# SparkFun_Transceiver_Breakout_RPSMA.net
KiCad netlist of a schematic drawn in EAGLE
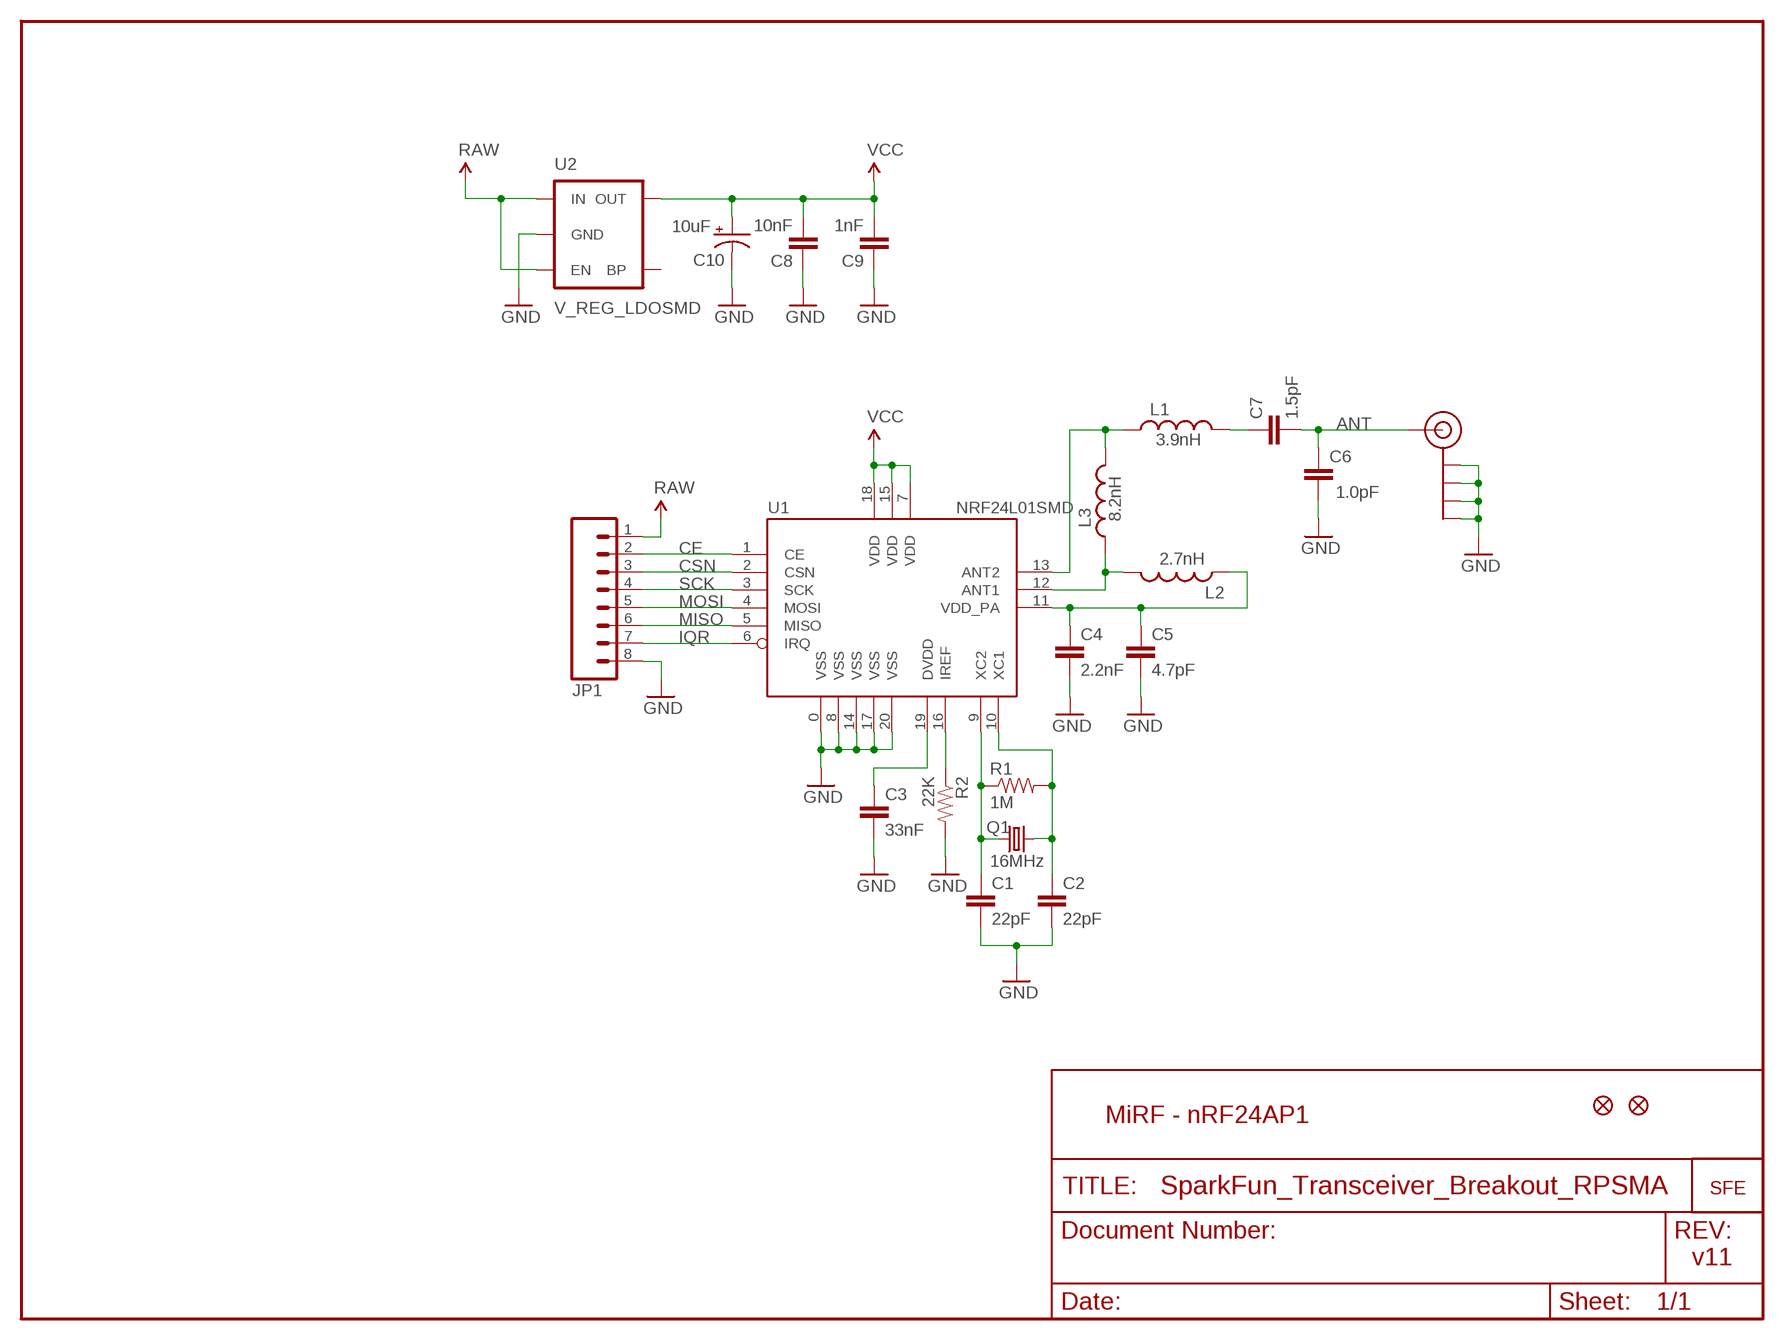
[diagram p0: schematic, sheet 1]

(export (version "E")
  (design (tool "Eeschema 10.0.6"))
  (components
    (comp (ref "C1")
      (value "22pF")
      (footprint "eagle-import:C0402")
      (libsource (lib "eagle-import") (part "CAP0402"))
    )
    (comp (ref "C2")
      (value "22pF")
      (footprint "eagle-import:C0402")
      (libsource (lib "eagle-import") (part "CAP0402"))
    )
    (comp (ref "C3")
      (value "33nF")
      (footprint "eagle-import:C0402")
      (libsource (lib "eagle-import") (part "CAP0402"))
    )
    (comp (ref "C4")
      (value "2.2nF")
      (footprint "eagle-import:C0402")
      (libsource (lib "eagle-import") (part "CAP0402"))
    )
    (comp (ref "C5")
      (value "4.7pF")
      (footprint "eagle-import:C0402")
      (libsource (lib "eagle-import") (part "CAP0402"))
    )
    (comp (ref "C6")
      (value "1.0pF")
      (footprint "eagle-import:C0402")
      (libsource (lib "eagle-import") (part "CAP0402"))
    )
    (comp (ref "C7")
      (value "1.5pF")
      (footprint "eagle-import:C0402")
      (libsource (lib "eagle-import") (part "CAP0402"))
    )
    (comp (ref "C8")
      (value "10nF")
      (footprint "eagle-import:C0402")
      (libsource (lib "eagle-import") (part "CAP0402"))
    )
    (comp (ref "C9")
      (value "1nF")
      (footprint "eagle-import:C0402")
      (libsource (lib "eagle-import") (part "CAP0402"))
    )
    (comp (ref "C10")
      (value "10uF")
      (footprint "eagle-import:EIA3216")
      (libsource (lib "eagle-import") (part "CAP_POL1206"))
    )
    (comp (ref "FID1")
      (value "FIDUCIALUFIDUCIAL")
      (footprint "eagle-import:MICRO-FIDUCIAL")
      (libsource (lib "eagle-import") (part "FIDUCIALUFIDUCIAL"))
    )
    (comp (ref "FID2")
      (value "FIDUCIALUFIDUCIAL")
      (footprint "eagle-import:MICRO-FIDUCIAL")
      (libsource (lib "eagle-import") (part "FIDUCIALUFIDUCIAL"))
    )
    (comp (ref "J$1")
      (value "SMA_EDGE")
      (footprint "eagle-import:SMA-EDGE")
      (libsource (lib "eagle-import") (part "SMA_EDGE"))
    )
    (comp (ref "JP1")
      (value "M08")
      (footprint "eagle-import:1X08")
      (libsource (lib "eagle-import") (part "M08"))
    )
    (comp (ref "L1")
      (value "3.9nH")
      (footprint "eagle-import:C0402")
      (libsource (lib "eagle-import") (part "INDUCTOR0402"))
    )
    (comp (ref "L2")
      (value "2.7nH")
      (footprint "eagle-import:C0402")
      (libsource (lib "eagle-import") (part "INDUCTOR0402"))
    )
    (comp (ref "L3")
      (value "8.2nH")
      (footprint "eagle-import:C0402")
      (libsource (lib "eagle-import") (part "INDUCTOR0402"))
    )
    (comp (ref "Q1")
      (value "16MHz")
      (footprint "eagle-import:CRYSTAL-SMD-5X3")
      (libsource (lib "eagle-import") (part "CRYSTAL5X3"))
    )
    (comp (ref "R1")
      (value "1M")
      (footprint "eagle-import:C0402")
      (libsource (lib "eagle-import") (part "RESISTOR0402"))
    )
    (comp (ref "R2")
      (value "22K")
      (footprint "eagle-import:C0402")
      (libsource (lib "eagle-import") (part "RESISTOR0402"))
    )
    (comp (ref "U$5")
      (value "LOGO-SFENEW")
      (footprint "eagle-import:SFE-NEW-WEBLOGO")
      (libsource (lib "eagle-import") (part "LOGO-SFENEW"))
    )
    (comp (ref "U1")
      (value "NRF24L01SMD")
      (footprint "eagle-import:QFN20")
      (libsource (lib "eagle-import") (part "NRF24L01SMD"))
    )
    (comp (ref "U2")
      (value "V_REG_LDOSMD")
      (footprint "eagle-import:SOT23-5")
      (libsource (lib "eagle-import") (part "V_REG_LDOSMD"))
    )
  )
  (nets
    (net (code "1") (name "/ANT") (class "Default")
      (node (ref "C6") (pin "2") (pinfunction "2_2") (pintype "passive"))
      (node (ref "C7") (pin "2") (pinfunction "2_2") (pintype "passive"))
      (node (ref "J$1") (pin "SIG") (pinfunction "SIGNAL_SIG") (pintype "bidirectional"))
    )
    (net (code "2") (name "/CE") (class "Default")
      (node (ref "JP1") (pin "2") (pinfunction "2_2") (pintype "passive"))
      (node (ref "U1") (pin "1") (pinfunction "CE_1") (pintype "input"))
    )
    (net (code "3") (name "/CSN") (class "Default")
      (node (ref "JP1") (pin "3") (pinfunction "3_3") (pintype "passive"))
      (node (ref "U1") (pin "2") (pinfunction "CSN_2") (pintype "input"))
    )
    (net (code "4") (name "/IQR") (class "Default")
      (node (ref "JP1") (pin "7") (pinfunction "7_7") (pintype "passive"))
      (node (ref "U1") (pin "6") (pinfunction "IRQ_6") (pintype "output"))
    )
    (net (code "5") (name "/MISO") (class "Default")
      (node (ref "JP1") (pin "6") (pinfunction "6_6") (pintype "passive"))
      (node (ref "U1") (pin "5") (pinfunction "MISO_5") (pintype "output"))
    )
    (net (code "6") (name "/MOSI") (class "Default")
      (node (ref "JP1") (pin "5") (pinfunction "5_5") (pintype "passive"))
      (node (ref "U1") (pin "4") (pinfunction "MOSI_4") (pintype "input"))
    )
    (net (code "7") (name "/SCK") (class "Default")
      (node (ref "JP1") (pin "4") (pinfunction "4_4") (pintype "passive"))
      (node (ref "U1") (pin "3") (pinfunction "SCK_3") (pintype "input"))
    )
    (net (code "8") (name "GND") (class "Default")
      (node (ref "C1") (pin "2") (pinfunction "2_2") (pintype "passive"))
      (node (ref "C10") (pin "C") (pinfunction "-_C") (pintype "passive"))
      (node (ref "C2") (pin "2") (pinfunction "2_2") (pintype "passive"))
      (node (ref "C3") (pin "2") (pinfunction "2_2") (pintype "passive"))
      (node (ref "C4") (pin "2") (pinfunction "2_2") (pintype "passive"))
      (node (ref "C5") (pin "2") (pinfunction "2_2") (pintype "passive"))
      (node (ref "C6") (pin "1") (pinfunction "1_1") (pintype "passive"))
      (node (ref "C8") (pin "1") (pinfunction "1_1") (pintype "passive"))
      (node (ref "C9") (pin "1") (pinfunction "1_1") (pintype "passive"))
      (node (ref "J$1") (pin "GND@0") (pinfunction "GND_GND@0") (pintype "bidirectional"))
      (node (ref "J$1") (pin "GND@1") (pinfunction "GND_GND@1") (pintype "bidirectional"))
      (node (ref "J$1") (pin "GND@2") (pinfunction "GND_GND@2") (pintype "bidirectional"))
      (node (ref "J$1") (pin "GND@3") (pinfunction "GND_GND@3") (pintype "bidirectional"))
      (node (ref "JP1") (pin "8") (pinfunction "8_8") (pintype "passive"))
      (node (ref "R2") (pin "2") (pinfunction "2_2") (pintype "passive"))
      (node (ref "U1") (pin "0") (pinfunction "VSS_0") (pintype "power_in"))
      (node (ref "U1") (pin "14") (pinfunction "VSS_14") (pintype "power_in"))
      (node (ref "U1") (pin "17") (pinfunction "VSS_17") (pintype "power_in"))
      (node (ref "U1") (pin "20") (pinfunction "VSS_20") (pintype "power_in"))
      (node (ref "U1") (pin "8") (pinfunction "VSS_8") (pintype "power_in"))
      (node (ref "U2") (pin "2") (pinfunction "GND_2") (pintype "input"))
    )
    (net (code "9") (name "Net-(C7-Pad1)") (class "Default")
      (node (ref "C7") (pin "1") (pinfunction "1_1") (pintype "passive"))
      (node (ref "L1") (pin "2") (pinfunction "2_2") (pintype "passive"))
    )
    (net (code "10") (name "Net-(Q1-2)") (class "Default")
      (node (ref "C2") (pin "1") (pinfunction "1_1") (pintype "passive"))
      (node (ref "Q1") (pin "3") (pinfunction "2_3") (pintype "passive"))
      (node (ref "R1") (pin "2") (pinfunction "2_2") (pintype "passive"))
      (node (ref "U1") (pin "10") (pinfunction "XC1_10") (pintype "input"))
    )
    (net (code "11") (name "Net-(U1-ANT1)") (class "Default")
      (node (ref "L2") (pin "2") (pinfunction "2_2") (pintype "passive"))
      (node (ref "L3") (pin "1") (pinfunction "1_1") (pintype "passive"))
      (node (ref "U1") (pin "12") (pinfunction "ANT1_12") (pintype "output"))
    )
    (net (code "12") (name "Net-(U1-ANT2)") (class "Default")
      (node (ref "L1") (pin "1") (pinfunction "1_1") (pintype "passive"))
      (node (ref "L3") (pin "2") (pinfunction "2_2") (pintype "passive"))
      (node (ref "U1") (pin "13") (pinfunction "ANT2_13") (pintype "output"))
    )
    (net (code "13") (name "Net-(U1-DVDD)") (class "Default")
      (node (ref "C3") (pin "1") (pinfunction "1_1") (pintype "passive"))
      (node (ref "U1") (pin "19") (pinfunction "DVDD_19") (pintype "power_in"))
    )
    (net (code "14") (name "Net-(U1-IREF)") (class "Default")
      (node (ref "R2") (pin "1") (pinfunction "1_1") (pintype "passive"))
      (node (ref "U1") (pin "16") (pinfunction "IREF_16") (pintype "input"))
    )
    (net (code "15") (name "Net-(U1-VDD_PA)") (class "Default")
      (node (ref "C4") (pin "1") (pinfunction "1_1") (pintype "passive"))
      (node (ref "C5") (pin "1") (pinfunction "1_1") (pintype "passive"))
      (node (ref "L2") (pin "1") (pinfunction "1_1") (pintype "passive"))
      (node (ref "U1") (pin "11") (pinfunction "VDD_PA_11") (pintype "power_in"))
    )
    (net (code "16") (name "Net-(U1-XC2)") (class "Default")
      (node (ref "C1") (pin "1") (pinfunction "1_1") (pintype "passive"))
      (node (ref "Q1") (pin "1") (pinfunction "1_1") (pintype "passive"))
      (node (ref "R1") (pin "1") (pinfunction "1_1") (pintype "passive"))
      (node (ref "U1") (pin "9") (pinfunction "XC2_9") (pintype "input"))
    )
    (net (code "17") (name "RAW") (class "Default")
      (node (ref "JP1") (pin "1") (pinfunction "1_1") (pintype "passive"))
      (node (ref "U2") (pin "1") (pinfunction "IN_1") (pintype "input"))
      (node (ref "U2") (pin "3") (pinfunction "EN_3") (pintype "input"))
    )
    (net (code "18") (name "VCC") (class "Default")
      (node (ref "C10") (pin "A") (pinfunction "+_A") (pintype "passive"))
      (node (ref "C8") (pin "2") (pinfunction "2_2") (pintype "passive"))
      (node (ref "C9") (pin "2") (pinfunction "2_2") (pintype "passive"))
      (node (ref "U1") (pin "15") (pinfunction "VDD_15") (pintype "power_in"))
      (node (ref "U1") (pin "18") (pinfunction "VDD_18") (pintype "power_in"))
      (node (ref "U1") (pin "7") (pinfunction "VDD_7") (pintype "power_in"))
      (node (ref "U2") (pin "5") (pinfunction "OUT_5") (pintype "passive"))
    )
    (net (code "19") (name "unconnected-(U2-BP-Pad4)") (class "Default")
      (node (ref "U2") (pin "4") (pinfunction "BP_4") (pintype "input"))
    )
  )
)
